# Rectifire_PFC_Solar.net
KiCad netlist of a schematic drawn in Altium Designer
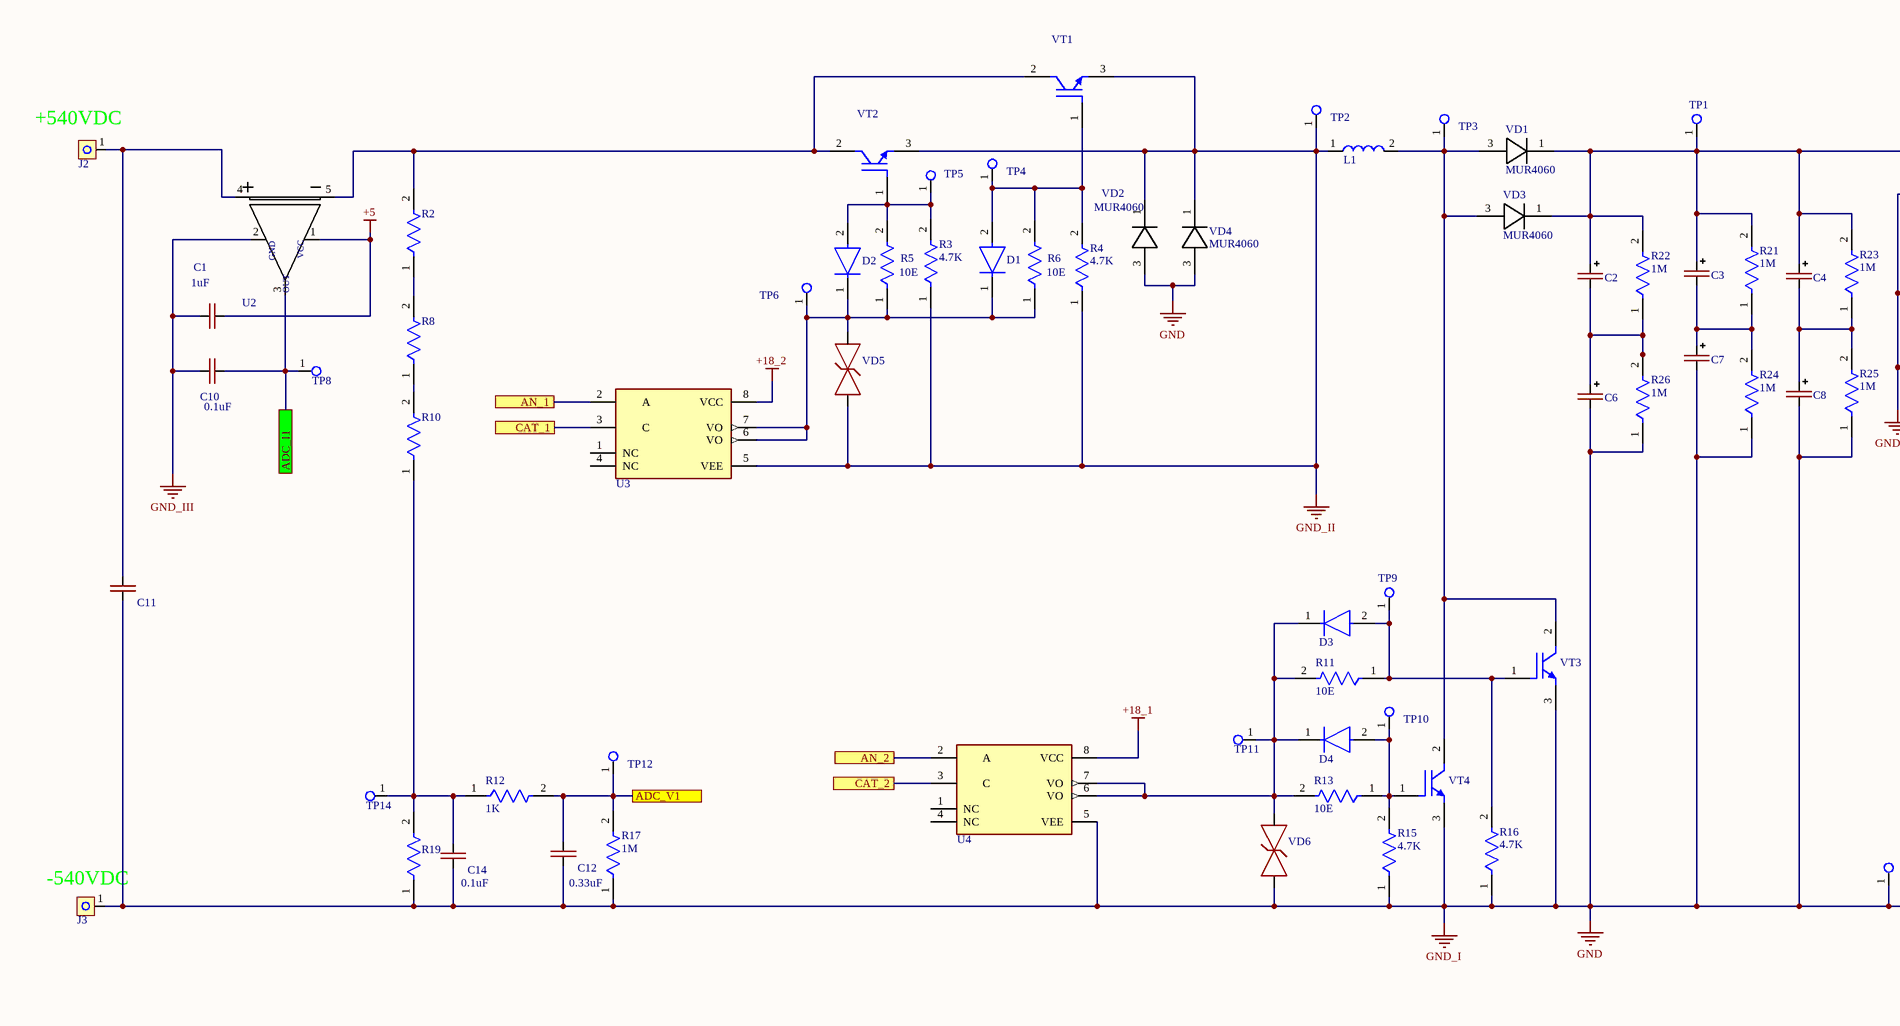
[diagram p0: Rectifire_PFC_Solar.SchDoc, top left]
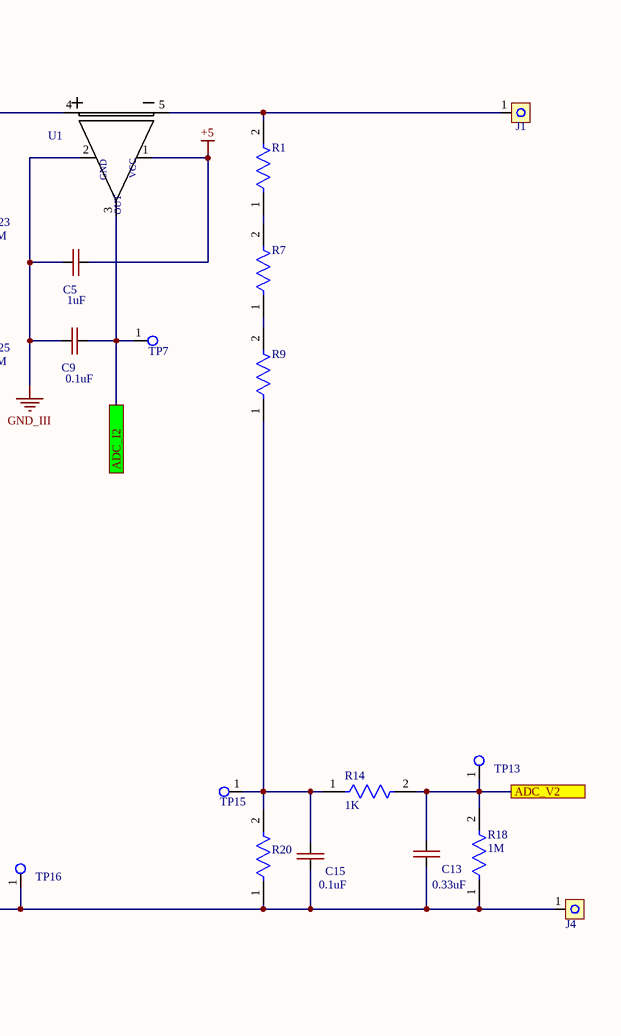
[diagram p1: Rectifire_PFC_Solar.SchDoc, top right]
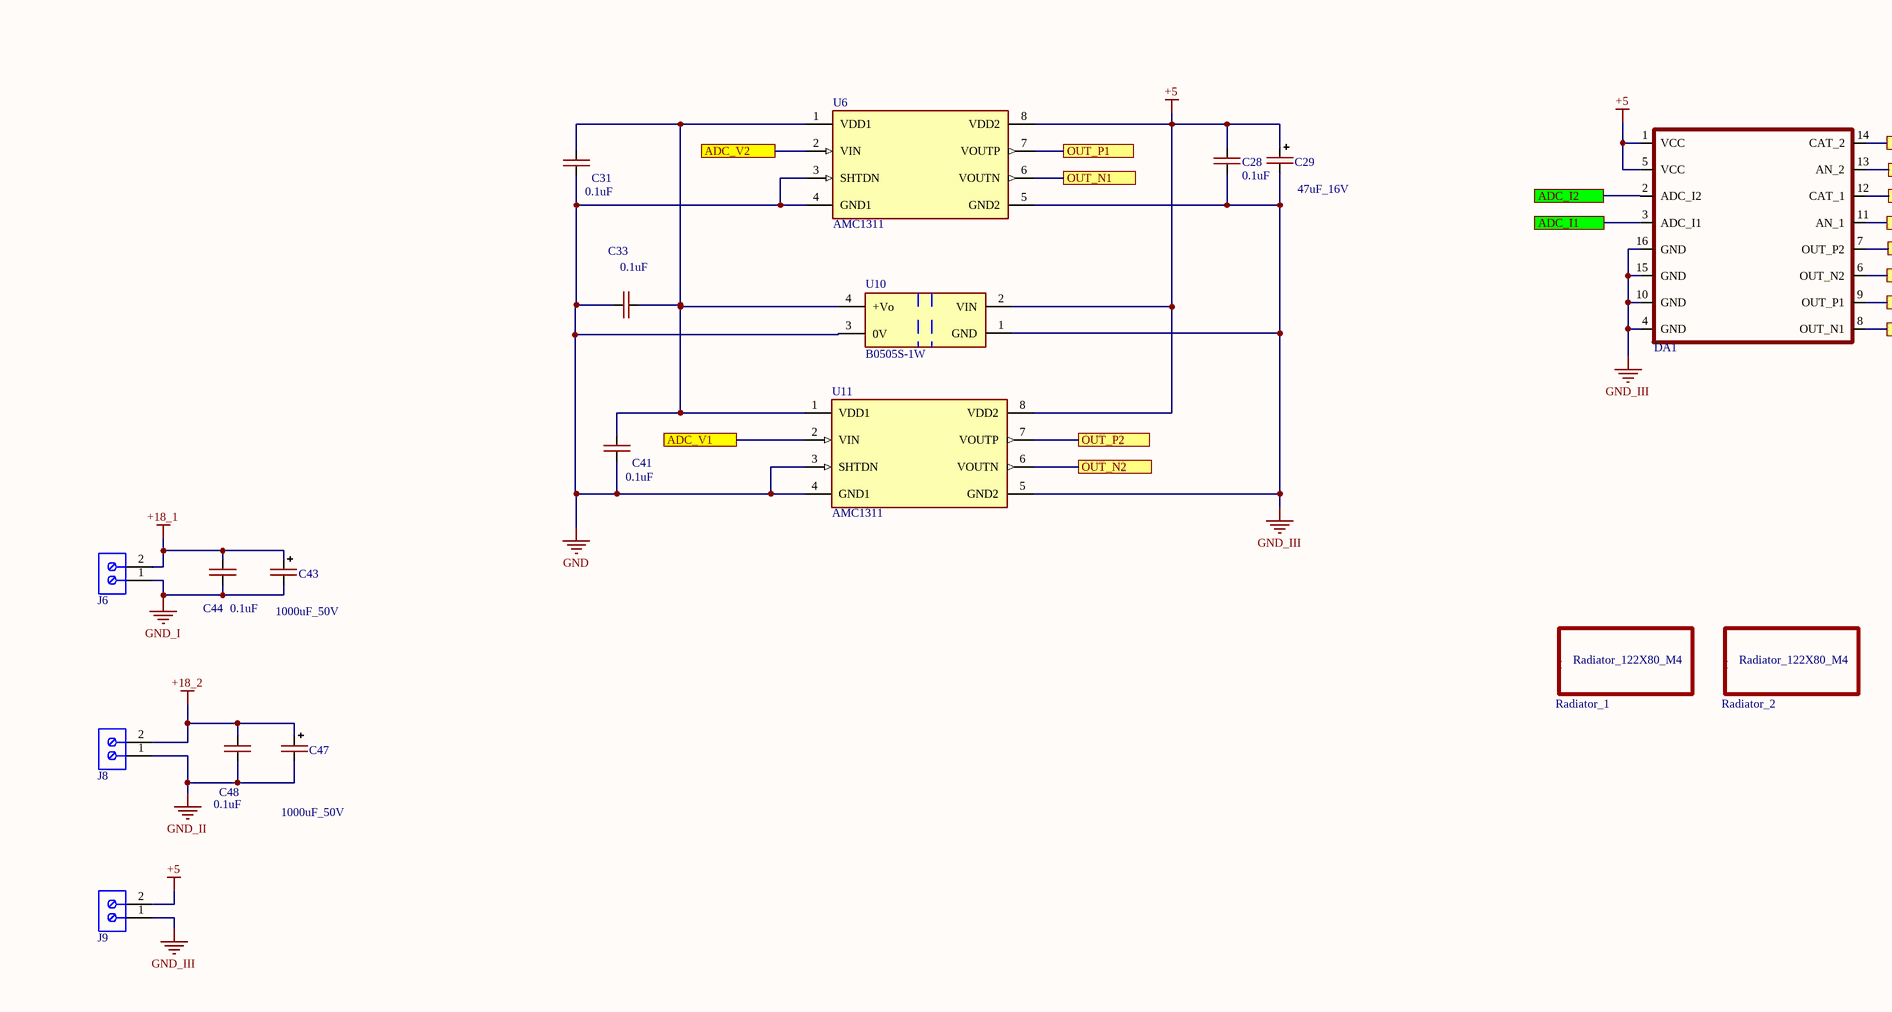
[diagram p2: Rectifire_PFC_Solar.SchDoc, bottom left]
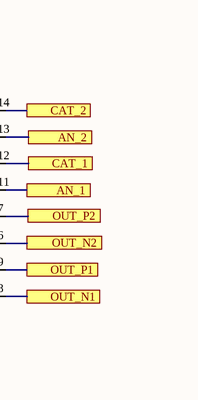
[diagram p3: Rectifire_PFC_Solar.SchDoc, bottom right]

(export (version "E")
  (design (tool "Eeschema 10.0.6"))
  (components
    (comp (ref "C1")
      (value "1uF")
      (footprint "CAP-0805")
      (libsource (lib "PASSIVE_COMPONENTS") (part "CAP-NON-POLAR"))
    )
    (comp (ref "C2")
      (value "CAP-POLAR")
      (footprint "CAP 100uF_500V 22x40mm")
      (libsource (lib "PASSIVE_COMPONENTS") (part "CAP-POLAR"))
    )
    (comp (ref "C3")
      (value "CAP-POLAR")
      (footprint "CAP 100uF_500V 22x40mm")
      (libsource (lib "PASSIVE_COMPONENTS") (part "CAP-POLAR"))
    )
    (comp (ref "C4")
      (value "CAP-POLAR")
      (footprint "CAP 100uF_500V 22x40mm")
      (libsource (lib "PASSIVE_COMPONENTS") (part "CAP-POLAR"))
    )
    (comp (ref "C5")
      (value "1uF")
      (footprint "CAP-0805")
      (libsource (lib "PASSIVE_COMPONENTS") (part "CAP-NON-POLAR"))
    )
    (comp (ref "C6")
      (value "CAP-POLAR")
      (footprint "CAP 100uF_500V 22x40mm")
      (libsource (lib "PASSIVE_COMPONENTS") (part "CAP-POLAR"))
    )
    (comp (ref "C7")
      (value "CAP-POLAR")
      (footprint "CAP 100uF_500V 22x40mm")
      (libsource (lib "PASSIVE_COMPONENTS") (part "CAP-POLAR"))
    )
    (comp (ref "C8")
      (value "CAP-POLAR")
      (footprint "CAP 100uF_500V 22x40mm")
      (libsource (lib "PASSIVE_COMPONENTS") (part "CAP-POLAR"))
    )
    (comp (ref "C9")
      (value "0.1uF")
      (footprint "CAP-0805")
      (libsource (lib "PASSIVE_COMPONENTS") (part "CAP-NON-POLAR"))
    )
    (comp (ref "C10")
      (value "0.1uF")
      (footprint "CAP-0805")
      (libsource (lib "PASSIVE_COMPONENTS") (part "CAP-NON-POLAR"))
    )
    (comp (ref "C11")
      (value "CAP-NON-POLAR")
      (footprint "CAP_4.7uF_630V")
      (libsource (lib "PASSIVE_COMPONENTS") (part "CAP-NON-POLAR"))
    )
    (comp (ref "C12")
      (value "0.33uF")
      (footprint "CAP-0805")
      (libsource (lib "PASSIVE_COMPONENTS") (part "CAP-NON-POLAR"))
    )
    (comp (ref "C13")
      (value "0.33uF")
      (footprint "CAP-0805")
      (libsource (lib "PASSIVE_COMPONENTS") (part "CAP-NON-POLAR"))
    )
    (comp (ref "C14")
      (value "0.1uF")
      (footprint "CAP-0805")
      (libsource (lib "PASSIVE_COMPONENTS") (part "CAP-NON-POLAR"))
    )
    (comp (ref "C15")
      (value "0.1uF")
      (footprint "CAP-0805")
      (libsource (lib "PASSIVE_COMPONENTS") (part "CAP-NON-POLAR"))
    )
    (comp (ref "C28")
      (value "0.1uF")
      (footprint "CAP-0805")
      (libsource (lib "PASSIVE_COMPONENTS") (part "CAP-NON-POLAR"))
    )
    (comp (ref "C29")
      (value "47uF_16V")
      (footprint "CAP-TAN-D")
      (libsource (lib "PASSIVE_COMPONENTS") (part "CAP-POLAR"))
    )
    (comp (ref "C31")
      (value "0.1uF")
      (footprint "CAP-0805")
      (libsource (lib "PASSIVE_COMPONENTS") (part "CAP-NON-POLAR"))
    )
    (comp (ref "C33")
      (value "0.1uF")
      (footprint "CAP-0805")
      (libsource (lib "PASSIVE_COMPONENTS") (part "CAP-NON-POLAR"))
    )
    (comp (ref "C41")
      (value "0.1uF")
      (footprint "CAP-0805")
      (libsource (lib "PASSIVE_COMPONENTS") (part "CAP-NON-POLAR"))
    )
    (comp (ref "C43")
      (value "1000uF_50V")
      (footprint "CAPPOL-16x25")
      (libsource (lib "PASSIVE_COMPONENTS") (part "CAP-POLAR"))
    )
    (comp (ref "C44")
      (value "0.1uF")
      (footprint "CAP-0805")
      (libsource (lib "PASSIVE_COMPONENTS") (part "CAP-NON-POLAR"))
    )
    (comp (ref "C47")
      (value "1000uF_50V")
      (footprint "CAPPOL-16x25")
      (libsource (lib "PASSIVE_COMPONENTS") (part "CAP-POLAR"))
    )
    (comp (ref "C48")
      (value "0.1uF")
      (footprint "CAP-0805")
      (libsource (lib "PASSIVE_COMPONENTS") (part "CAP-NON-POLAR"))
    )
    (comp (ref "D1") (value "US1G") (footprint "DO-214AA") (libsource (lib "Diodes") (part "US1G")))
    (comp (ref "D2") (value "US1G") (footprint "DO-214AA") (libsource (lib "Diodes") (part "US1G")))
    (comp (ref "D3") (value "US1G") (footprint "DO-214AA") (libsource (lib "Diodes") (part "US1G")))
    (comp (ref "D4") (value "US1G") (footprint "DO-214AA") (libsource (lib "Diodes") (part "US1G")))
    (comp (ref "DA1")
      (value "BOARD_PFC")
      (footprint "BOARD_PFC")
      (libsource (lib "BOARD_PFC") (part "BOARD_PFC"))
    )
    (comp (ref "J1")
      (value "MG_136_HT")
      (footprint "Conn_MEIGAN_MG136HT")
      (libsource (lib "") (part "Connector_MEIGAN_MG136HT_1"))
    )
    (comp (ref "J2")
      (value "MG_136_HT")
      (footprint "Conn_MEIGAN_MG136HT")
      (libsource (lib "Connectors") (part "Connector_MEIGAN_MG136HT"))
    )
    (comp (ref "J3")
      (value "MG_136_HT")
      (footprint "Conn_MEIGAN_MG136HT")
      (libsource (lib "Connectors") (part "Connector_MEIGAN_MG136HT"))
    )
    (comp (ref "J4")
      (value "MG_136_HT")
      (footprint "Conn_MEIGAN_MG136HT")
      (libsource (lib "") (part "Connector_MEIGAN_MG136HT_1"))
    )
    (comp (ref "J6")
      (value "691102710002")
      (footprint "691102710002")
      (description "WR-TBL Series 102 Horizontal Entry Modular, THT, pitch 5mm, 2p")
      (fields (field (name "MANUFACTURER") "Wurth Elektronik"))
      (libsource (lib "Altium_WR-TBL (rev23f)") (part "691102710002"))
    )
    (comp (ref "J8")
      (value "691102710002")
      (footprint "691102710002")
      (description "WR-TBL Series 102 Horizontal Entry Modular, THT, pitch 5mm, 2p")
      (fields (field (name "MANUFACTURER") "Wurth Elektronik"))
      (libsource (lib "Altium_WR-TBL (rev23f)") (part "691102710002"))
    )
    (comp (ref "J9")
      (value "691102710002")
      (footprint "691102710002")
      (description "WR-TBL Series 102 Horizontal Entry Modular, THT, pitch 5mm, 2p")
      (fields (field (name "MANUFACTURER") "Wurth Elektronik"))
      (libsource (lib "Altium_WR-TBL (rev23f)") (part "691102710002"))
    )
    (comp (ref "L1") (value "Coil") (footprint "30A_10uH") (libsource (lib "Transformers") (part "Coil")))
    (comp (ref "R1")
      (value "~")
      (footprint "RES-2512")
      (libsource (lib "PASSIVE_COMPONENTS") (part "RES-CONST"))
    )
    (comp (ref "R2")
      (value "~")
      (footprint "RES-2512")
      (libsource (lib "PASSIVE_COMPONENTS") (part "RES-CONST"))
    )
    (comp (ref "R3")
      (value "4.7K")
      (footprint "RES-0805")
      (libsource (lib "PASSIVE_COMPONENTS") (part "RES-CONST"))
    )
    (comp (ref "R4")
      (value "4.7K")
      (footprint "RES-0805")
      (libsource (lib "PASSIVE_COMPONENTS") (part "RES-CONST"))
    )
    (comp (ref "R5")
      (value "10E")
      (footprint "RES_SMD_1210_IPC_A")
      (libsource (lib "PASSIVE_COMPONENTS") (part "RES_1210"))
    )
    (comp (ref "R6")
      (value "10E")
      (footprint "RES_SMD_1210_IPC_A")
      (libsource (lib "PASSIVE_COMPONENTS") (part "RES_1210"))
    )
    (comp (ref "R7")
      (value "~")
      (footprint "RES-2512")
      (libsource (lib "PASSIVE_COMPONENTS") (part "RES-CONST"))
    )
    (comp (ref "R8")
      (value "~")
      (footprint "RES-2512")
      (libsource (lib "PASSIVE_COMPONENTS") (part "RES-CONST"))
    )
    (comp (ref "R9")
      (value "~")
      (footprint "RES-2512")
      (libsource (lib "PASSIVE_COMPONENTS") (part "RES-CONST"))
    )
    (comp (ref "R10")
      (value "~")
      (footprint "RES-2512")
      (libsource (lib "PASSIVE_COMPONENTS") (part "RES-CONST"))
    )
    (comp (ref "R11")
      (value "10E")
      (footprint "RES_SMD_1210_IPC_A")
      (libsource (lib "PASSIVE_COMPONENTS") (part "RES_1210"))
    )
    (comp (ref "R12")
      (value "1K")
      (footprint "RES-0805")
      (libsource (lib "PASSIVE_COMPONENTS") (part "RES-CONST"))
    )
    (comp (ref "R13")
      (value "10E")
      (footprint "RES_SMD_1210_IPC_A")
      (libsource (lib "PASSIVE_COMPONENTS") (part "RES_1210"))
    )
    (comp (ref "R14")
      (value "1K")
      (footprint "RES-0805")
      (libsource (lib "PASSIVE_COMPONENTS") (part "RES-CONST"))
    )
    (comp (ref "R15")
      (value "4.7K")
      (footprint "RES-0805")
      (libsource (lib "PASSIVE_COMPONENTS") (part "RES-CONST"))
    )
    (comp (ref "R16")
      (value "4.7K")
      (footprint "RES-0805")
      (libsource (lib "PASSIVE_COMPONENTS") (part "RES-CONST"))
    )
    (comp (ref "R17")
      (value "1M")
      (footprint "RES-0805")
      (libsource (lib "PASSIVE_COMPONENTS") (part "RES-CONST"))
    )
    (comp (ref "R18")
      (value "1M")
      (footprint "RES-0805")
      (libsource (lib "PASSIVE_COMPONENTS") (part "RES-CONST"))
    )
    (comp (ref "R19")
      (value "RES_1210")
      (footprint "RES_SMD_1210_IPC_B")
      (libsource (lib "PASSIVE_COMPONENTS") (part "RES_1210"))
    )
    (comp (ref "R20")
      (value "RES_1210")
      (footprint "RES_SMD_1210_IPC_B")
      (libsource (lib "PASSIVE_COMPONENTS") (part "RES_1210"))
    )
    (comp (ref "R21")
      (value "1M")
      (footprint "RES-2512")
      (description "4.7K")
      (libsource (lib "PASSIVE_COMPONENTS") (part "RES-CONST"))
    )
    (comp (ref "R22")
      (value "1M")
      (footprint "RES-2512")
      (description "4.7K")
      (libsource (lib "PASSIVE_COMPONENTS") (part "RES-CONST"))
    )
    (comp (ref "R23")
      (value "1M")
      (footprint "RES-2512")
      (description "4.7K")
      (libsource (lib "PASSIVE_COMPONENTS") (part "RES-CONST"))
    )
    (comp (ref "R24")
      (value "1M")
      (footprint "RES-2512")
      (description "4.7K")
      (libsource (lib "PASSIVE_COMPONENTS") (part "RES-CONST"))
    )
    (comp (ref "R25")
      (value "1M")
      (footprint "RES-2512")
      (description "4.7K")
      (libsource (lib "PASSIVE_COMPONENTS") (part "RES-CONST"))
    )
    (comp (ref "R26")
      (value "1M")
      (footprint "RES-2512")
      (description "4.7K")
      (libsource (lib "PASSIVE_COMPONENTS") (part "RES-CONST"))
    )
    (comp (ref "Radiator_1")
      (value "Radiator_122X80_M4")
      (footprint "Radiator_122X80_M4")
      (libsource (lib "Radiator_122X80_M4") (part "Radiator_122X80_M4"))
    )
    (comp (ref "Radiator_2")
      (value "Radiator_122X80_M4")
      (footprint "Radiator_122X80_M4")
      (libsource (lib "Radiator_122X80_M4") (part "Radiator_122X80_M4"))
    )
    (comp (ref "TP1")
      (value "Test_Point_PCB")
      (footprint "Test_Point")
      (description "Test_Point")
      (libsource (lib "Connectors") (part "TP_PCB?"))
    )
    (comp (ref "TP2")
      (value "Test_Point_PCB")
      (footprint "Test_Point")
      (description "Test_Point")
      (libsource (lib "Connectors") (part "TP_PCB?"))
    )
    (comp (ref "TP3")
      (value "Test_Point_PCB")
      (footprint "Test_Point")
      (description "Test_Point")
      (libsource (lib "Connectors") (part "TP_PCB?"))
    )
    (comp (ref "TP4")
      (value "Test_Point_PCB")
      (footprint "Test_Point")
      (description "Test_Point")
      (libsource (lib "Connectors") (part "TP_PCB?"))
    )
    (comp (ref "TP5")
      (value "Test_Point_PCB")
      (footprint "Test_Point")
      (description "Test_Point")
      (libsource (lib "Connectors") (part "TP_PCB?"))
    )
    (comp (ref "TP6")
      (value "Test_Point_PCB")
      (footprint "Test_Point")
      (description "Test_Point")
      (libsource (lib "Connectors") (part "TP_PCB?"))
    )
    (comp (ref "TP7")
      (value "Test_Point_PCB")
      (footprint "Test_Point")
      (description "Test_Point")
      (libsource (lib "Connectors") (part "TP_PCB?"))
    )
    (comp (ref "TP8")
      (value "Test_Point_PCB")
      (footprint "Test_Point")
      (description "Test_Point")
      (libsource (lib "Connectors") (part "TP_PCB?"))
    )
    (comp (ref "TP9")
      (value "Test_Point_PCB")
      (footprint "Test_Point")
      (description "Test_Point")
      (libsource (lib "Connectors") (part "TP_PCB?"))
    )
    (comp (ref "TP10")
      (value "Test_Point_PCB")
      (footprint "Test_Point")
      (description "Test_Point")
      (libsource (lib "Connectors") (part "TP_PCB?"))
    )
    (comp (ref "TP11")
      (value "Test_Point_PCB")
      (footprint "Test_Point")
      (description "Test_Point")
      (libsource (lib "Connectors") (part "TP_PCB?"))
    )
    (comp (ref "TP12")
      (value "Test_Point_PCB")
      (footprint "Test_Point")
      (description "Test_Point")
      (libsource (lib "Connectors") (part "TP_PCB?"))
    )
    (comp (ref "TP13")
      (value "Test_Point_PCB")
      (footprint "Test_Point")
      (description "Test_Point")
      (libsource (lib "Connectors") (part "TP_PCB?"))
    )
    (comp (ref "TP14")
      (value "Test_Point_PCB")
      (footprint "Test_Point")
      (description "Test_Point")
      (libsource (lib "Connectors") (part "TP_PCB?"))
    )
    (comp (ref "TP15")
      (value "Test_Point_PCB")
      (footprint "Test_Point")
      (description "Test_Point")
      (libsource (lib "Connectors") (part "TP_PCB?"))
    )
    (comp (ref "TP16")
      (value "Test_Point_PCB")
      (footprint "Test_Point")
      (description "Test_Point")
      (libsource (lib "Connectors") (part "TP_PCB?"))
    )
    (comp (ref "U1")
      (value "ACS758")
      (footprint "ACS758-100")
      (libsource (lib "Integrated_Circuts") (part "ACS758"))
    )
    (comp (ref "U2")
      (value "ACS758")
      (footprint "ACS758-100")
      (libsource (lib "Integrated_Circuts") (part "ACS758"))
    )
    (comp (ref "U3")
      (value "HCPL-3120")
      (footprint "HCPL-3120")
      (libsource (lib "Integrated_Circuts") (part "HCPL-3120"))
    )
    (comp (ref "U4")
      (value "HCPL-3120")
      (footprint "HCPL-3120")
      (libsource (lib "Integrated_Circuts") (part "HCPL-3120"))
    )
    (comp (ref "U6")
      (value "AMC1311")
      (footprint "FP-DWV0008A-MFG")
      (libsource (lib "Integrated_Circuts") (part "AMC1311"))
    )
    (comp (ref "U10")
      (value "B0505S-1W")
      (footprint "B0505S-1W")
      (libsource (lib "Integrated_Circuts") (part "B0505S-1W"))
    )
    (comp (ref "U11")
      (value "AMC1311")
      (footprint "FP-DWV0008A-MFG")
      (libsource (lib "Integrated_Circuts") (part "AMC1311"))
    )
    (comp (ref "VD1") (value "MUR4060") (footprint "TO-247-2") (libsource (lib "Diodes") (part "MUR4060")))
    (comp (ref "VD2") (value "MUR4060") (footprint "TO-247-2") (libsource (lib "Diodes") (part "MUR4060")))
    (comp (ref "VD3") (value "MUR4060") (footprint "TO-247-2") (libsource (lib "Diodes") (part "MUR4060")))
    (comp (ref "VD4") (value "MUR4060") (footprint "TO-247-2") (libsource (lib "Diodes") (part "MUR4060")))
    (comp (ref "VD5")
      (value "Suppressor")
      (footprint "DO-214AA")
      (libsource (lib "Diodes") (part "Suppressor"))
    )
    (comp (ref "VD6")
      (value "Suppressor")
      (footprint "DO-214AA")
      (libsource (lib "Diodes") (part "Suppressor"))
    )
    (comp (ref "VT1")
      (value "IGBT 60N120T")
      (footprint "TO-264-3")
      (description "IGBT 60N120T TO-264-3")
      (libsource (lib "Transistors") (part "IGBT 60N120T"))
    )
    (comp (ref "VT2")
      (value "IGBT 60N120T")
      (footprint "TO-264-3")
      (description "IGBT 60N120T TO-264-3")
      (libsource (lib "Transistors") (part "IGBT 60N120T"))
    )
    (comp (ref "VT3")
      (value "IGBT 60N120T")
      (footprint "TO-264-3")
      (description "IGBT 60N120T TO-264-3")
      (libsource (lib "Transistors") (part "IGBT 60N120T"))
    )
    (comp (ref "VT4")
      (value "IGBT 60N120T")
      (footprint "TO-264-3")
      (description "IGBT 60N120T TO-264-3")
      (libsource (lib "Transistors") (part "IGBT 60N120T"))
    )
  )
  (nets
    (net (code "1") (name "+5") (class "Default")
      (node (ref "C1") (pin "2") (pinfunction "2_2") (pintype "passive"))
      (node (ref "C28") (pin "1") (pinfunction "1_1") (pintype "passive"))
      (node (ref "C29") (pin "1") (pinfunction "+_1") (pintype "passive"))
      (node (ref "C5") (pin "2") (pinfunction "2_2") (pintype "passive"))
      (node (ref "DA1") (pin "1") (pinfunction "VCC_1") (pintype "passive"))
      (node (ref "DA1") (pin "5") (pinfunction "VCC_5") (pintype "passive"))
      (node (ref "J9") (pin "2") (pinfunction "2_2") (pintype "passive"))
      (node (ref "U1") (pin "1") (pinfunction "+VCC_1") (pintype "passive"))
      (node (ref "U10") (pin "2") (pinfunction "VIN_2") (pintype "power_in"))
      (node (ref "U11") (pin "8") (pinfunction "VDD2_8") (pintype "power_in"))
      (node (ref "U2") (pin "1") (pinfunction "+VCC_1") (pintype "passive"))
      (node (ref "U6") (pin "8") (pinfunction "VDD2_8") (pintype "power_in"))
    )
    (net (code "2") (name "+18_1") (class "Default")
      (node (ref "C43") (pin "1") (pinfunction "+_1") (pintype "passive"))
      (node (ref "C44") (pin "2") (pinfunction "2_2") (pintype "passive"))
      (node (ref "J6") (pin "2") (pinfunction "2_2") (pintype "passive"))
      (node (ref "U4") (pin "8") (pinfunction "VCC_8") (pintype "power_in"))
    )
    (net (code "3") (name "+18_2") (class "Default")
      (node (ref "C47") (pin "1") (pinfunction "+_1") (pintype "passive"))
      (node (ref "C48") (pin "2") (pinfunction "2_2") (pintype "passive"))
      (node (ref "J8") (pin "2") (pinfunction "2_2") (pintype "passive"))
      (node (ref "U3") (pin "8") (pinfunction "VCC_8") (pintype "power_in"))
    )
    (net (code "4") (name "/ADC_I1") (class "Default")
      (node (ref "C10") (pin "2") (pinfunction "2_2") (pintype "passive"))
      (node (ref "DA1") (pin "3") (pinfunction "ADC_I1_3") (pintype "passive"))
      (node (ref "TP8") (pin "1") (pinfunction "G9_1") (pintype "passive"))
      (node (ref "U2") (pin "3") (pinfunction "OUT_3") (pintype "passive"))
    )
    (net (code "5") (name "/ADC_I2") (class "Default")
      (node (ref "C9") (pin "2") (pinfunction "2_2") (pintype "passive"))
      (node (ref "DA1") (pin "2") (pinfunction "ADC_I2_2") (pintype "passive"))
      (node (ref "TP7") (pin "1") (pinfunction "G9_1") (pintype "passive"))
      (node (ref "U1") (pin "3") (pinfunction "OUT_3") (pintype "passive"))
    )
    (net (code "6") (name "/ADC_V1") (class "Default")
      (node (ref "C12") (pin "2") (pinfunction "2_2") (pintype "passive"))
      (node (ref "R12") (pin "2") (pinfunction "2_2") (pintype "passive"))
      (node (ref "R17") (pin "2") (pinfunction "2_2") (pintype "passive"))
      (node (ref "TP12") (pin "1") (pinfunction "G9_1") (pintype "passive"))
      (node (ref "U11") (pin "2") (pinfunction "VIN_2") (pintype "input"))
    )
    (net (code "7") (name "/ADC_V2") (class "Default")
      (node (ref "C13") (pin "2") (pinfunction "2_2") (pintype "passive"))
      (node (ref "R14") (pin "2") (pinfunction "2_2") (pintype "passive"))
      (node (ref "R18") (pin "2") (pinfunction "2_2") (pintype "passive"))
      (node (ref "TP13") (pin "1") (pinfunction "G9_1") (pintype "passive"))
      (node (ref "U6") (pin "2") (pinfunction "VIN_2") (pintype "input"))
    )
    (net (code "8") (name "/AN_1") (class "Default")
      (node (ref "DA1") (pin "11") (pinfunction "AN_1_11") (pintype "passive"))
      (node (ref "U3") (pin "2") (pinfunction "A_2") (pintype "passive"))
    )
    (net (code "9") (name "/AN_2") (class "Default")
      (node (ref "DA1") (pin "13") (pinfunction "AN_2_13") (pintype "passive"))
      (node (ref "U4") (pin "2") (pinfunction "A_2") (pintype "passive"))
    )
    (net (code "10") (name "/CAT_1") (class "Default")
      (node (ref "DA1") (pin "12") (pinfunction "CAT_1_12") (pintype "passive"))
      (node (ref "U3") (pin "3") (pinfunction "C_3") (pintype "passive"))
    )
    (net (code "11") (name "/CAT_2") (class "Default")
      (node (ref "DA1") (pin "14") (pinfunction "CAT_2_14") (pintype "passive"))
      (node (ref "U4") (pin "3") (pinfunction "C_3") (pintype "passive"))
    )
    (net (code "12") (name "/OUT_N1") (class "Default")
      (node (ref "DA1") (pin "8") (pinfunction "OUT_N1_8") (pintype "passive"))
      (node (ref "U6") (pin "6") (pinfunction "VOUTN_6") (pintype "output"))
    )
    (net (code "13") (name "/OUT_N2") (class "Default")
      (node (ref "DA1") (pin "6") (pinfunction "OUT_N2_6") (pintype "passive"))
      (node (ref "U11") (pin "6") (pinfunction "VOUTN_6") (pintype "output"))
    )
    (net (code "14") (name "/OUT_P1") (class "Default")
      (node (ref "DA1") (pin "9") (pinfunction "OUT_P1_9") (pintype "passive"))
      (node (ref "U6") (pin "7") (pinfunction "VOUTP_7") (pintype "output"))
    )
    (net (code "15") (name "/OUT_P2") (class "Default")
      (node (ref "DA1") (pin "7") (pinfunction "OUT_P2_7") (pintype "passive"))
      (node (ref "U11") (pin "7") (pinfunction "VOUTP_7") (pintype "output"))
    )
    (net (code "16") (name "GND") (class "Default")
      (node (ref "C11") (pin "1") (pinfunction "1_1") (pintype "passive"))
      (node (ref "C12") (pin "1") (pinfunction "1_1") (pintype "passive"))
      (node (ref "C13") (pin "1") (pinfunction "1_1") (pintype "passive"))
      (node (ref "C14") (pin "1") (pinfunction "1_1") (pintype "passive"))
      (node (ref "C15") (pin "1") (pinfunction "1_1") (pintype "passive"))
      (node (ref "C31") (pin "1") (pinfunction "1_1") (pintype "passive"))
      (node (ref "C33") (pin "2") (pinfunction "2_2") (pintype "passive"))
      (node (ref "C41") (pin "1") (pinfunction "1_1") (pintype "passive"))
      (node (ref "C43") (pin "2") (pinfunction "-_2") (pintype "passive"))
      (node (ref "C44") (pin "1") (pinfunction "1_1") (pintype "passive"))
      (node (ref "C6") (pin "2") (pinfunction "-_2") (pintype "passive"))
      (node (ref "C7") (pin "2") (pinfunction "-_2") (pintype "passive"))
      (node (ref "C8") (pin "2") (pinfunction "-_2") (pintype "passive"))
      (node (ref "J3") (pin "1") (pinfunction "17_1") (pintype "passive"))
      (node (ref "J4") (pin "1") (pinfunction "17_1") (pintype "passive"))
      (node (ref "J6") (pin "1") (pinfunction "1_1") (pintype "passive"))
      (node (ref "R15") (pin "1") (pinfunction "1_1") (pintype "passive"))
      (node (ref "R16") (pin "1") (pinfunction "1_1") (pintype "passive"))
      (node (ref "R17") (pin "1") (pinfunction "1_1") (pintype "passive"))
      (node (ref "R18") (pin "1") (pinfunction "1_1") (pintype "passive"))
      (node (ref "R19") (pin "1") (pinfunction "1_1") (pintype "passive"))
      (node (ref "R20") (pin "1") (pinfunction "1_1") (pintype "passive"))
      (node (ref "R24") (pin "1") (pinfunction "1_1") (pintype "passive"))
      (node (ref "R25") (pin "1") (pinfunction "1_1") (pintype "passive"))
      (node (ref "R26") (pin "1") (pinfunction "1_1") (pintype "passive"))
      (node (ref "TP16") (pin "1") (pinfunction "G9_1") (pintype "passive"))
      (node (ref "U10") (pin "3") (pinfunction "0V_3") (pintype "power_in"))
      (node (ref "U11") (pin "3") (pinfunction "SHTDN_3") (pintype "input"))
      (node (ref "U11") (pin "4") (pinfunction "GND1_4") (pintype "power_in"))
      (node (ref "U4") (pin "5") (pinfunction "VEE_5") (pintype "power_in"))
      (node (ref "U6") (pin "3") (pinfunction "SHTDN_3") (pintype "input"))
      (node (ref "U6") (pin "4") (pinfunction "GND1_4") (pintype "power_in"))
      (node (ref "VD2") (pin "3") (pinfunction "3_3") (pintype "passive"))
      (node (ref "VD4") (pin "3") (pinfunction "3_3") (pintype "passive"))
      (node (ref "VD6") (pin "1") (pinfunction "C_1") (pintype "passive"))
      (node (ref "VT3") (pin "3") (pinfunction "E_3") (pintype "passive"))
      (node (ref "VT4") (pin "3") (pinfunction "E_3") (pintype "passive"))
    )
    (net (code "17") (name "GND_II") (class "Default")
      (node (ref "C47") (pin "2") (pinfunction "-_2") (pintype "passive"))
      (node (ref "C48") (pin "1") (pinfunction "1_1") (pintype "passive"))
      (node (ref "J8") (pin "1") (pinfunction "1_1") (pintype "passive"))
      (node (ref "L1") (pin "1") (pinfunction "1_1") (pintype "passive"))
      (node (ref "R3") (pin "1") (pinfunction "1_1") (pintype "passive"))
      (node (ref "R4") (pin "1") (pinfunction "1_1") (pintype "passive"))
      (node (ref "TP2") (pin "1") (pinfunction "G9_1") (pintype "passive"))
      (node (ref "U3") (pin "5") (pinfunction "VEE_5") (pintype "power_in"))
      (node (ref "VD2") (pin "1") (pinfunction "1_1") (pintype "passive"))
      (node (ref "VD4") (pin "1") (pinfunction "1_1") (pintype "passive"))
      (node (ref "VD5") (pin "1") (pinfunction "C_1") (pintype "passive"))
      (node (ref "VT1") (pin "3") (pinfunction "E_3") (pintype "passive"))
      (node (ref "VT2") (pin "3") (pinfunction "E_3") (pintype "passive"))
    )
    (net (code "18") (name "GND_III") (class "Default")
      (node (ref "C1") (pin "1") (pinfunction "1_1") (pintype "passive"))
      (node (ref "C10") (pin "1") (pinfunction "1_1") (pintype "passive"))
      (node (ref "C28") (pin "2") (pinfunction "2_2") (pintype "passive"))
      (node (ref "C29") (pin "2") (pinfunction "-_2") (pintype "passive"))
      (node (ref "C5") (pin "1") (pinfunction "1_1") (pintype "passive"))
      (node (ref "C9") (pin "1") (pinfunction "1_1") (pintype "passive"))
      (node (ref "DA1") (pin "10") (pinfunction "GND_10") (pintype "passive"))
      (node (ref "DA1") (pin "15") (pinfunction "GND_15") (pintype "passive"))
      (node (ref "DA1") (pin "16") (pinfunction "GND_16") (pintype "passive"))
      (node (ref "DA1") (pin "4") (pinfunction "GND_4") (pintype "passive"))
      (node (ref "J9") (pin "1") (pinfunction "1_1") (pintype "passive"))
      (node (ref "U1") (pin "2") (pinfunction "GND_2") (pintype "passive"))
      (node (ref "U10") (pin "1") (pinfunction "GND_1") (pintype "power_in"))
      (node (ref "U11") (pin "5") (pinfunction "GND2_5") (pintype "power_in"))
      (node (ref "U2") (pin "2") (pinfunction "GND_2") (pintype "passive"))
      (node (ref "U6") (pin "5") (pinfunction "GND2_5") (pintype "power_in"))
    )
    (net (code "19") (name "Net-(C2-+)") (class "Default")
      (node (ref "C2") (pin "1") (pinfunction "+_1") (pintype "passive"))
      (node (ref "C3") (pin "1") (pinfunction "+_1") (pintype "passive"))
      (node (ref "C4") (pin "1") (pinfunction "+_1") (pintype "passive"))
      (node (ref "R21") (pin "2") (pinfunction "2_2") (pintype "passive"))
      (node (ref "R22") (pin "2") (pinfunction "2_2") (pintype "passive"))
      (node (ref "R23") (pin "2") (pinfunction "2_2") (pintype "passive"))
      (node (ref "TP1") (pin "1") (pinfunction "G9_1") (pintype "passive"))
      (node (ref "U1") (pin "4") (pinfunction "+IP_4") (pintype "passive"))
      (node (ref "VD1") (pin "1") (pinfunction "1_1") (pintype "passive"))
      (node (ref "VD3") (pin "1") (pinfunction "1_1") (pintype "passive"))
    )
    (net (code "20") (name "Net-(C2--)") (class "Default")
      (node (ref "C2") (pin "2") (pinfunction "-_2") (pintype "passive"))
      (node (ref "C6") (pin "1") (pinfunction "+_1") (pintype "passive"))
      (node (ref "R22") (pin "1") (pinfunction "1_1") (pintype "passive"))
      (node (ref "R26") (pin "2") (pinfunction "2_2") (pintype "passive"))
    )
    (net (code "21") (name "Net-(C3--)") (class "Default")
      (node (ref "C3") (pin "2") (pinfunction "-_2") (pintype "passive"))
      (node (ref "C7") (pin "1") (pinfunction "+_1") (pintype "passive"))
      (node (ref "R21") (pin "1") (pinfunction "1_1") (pintype "passive"))
      (node (ref "R24") (pin "2") (pinfunction "2_2") (pintype "passive"))
    )
    (net (code "22") (name "Net-(C4--)") (class "Default")
      (node (ref "C4") (pin "2") (pinfunction "-_2") (pintype "passive"))
      (node (ref "C8") (pin "1") (pinfunction "+_1") (pintype "passive"))
      (node (ref "R23") (pin "1") (pinfunction "1_1") (pintype "passive"))
      (node (ref "R25") (pin "2") (pinfunction "2_2") (pintype "passive"))
    )
    (net (code "23") (name "Net-(D1-A)") (class "Default")
      (node (ref "D1") (pin "2") (pinfunction "A_2") (pintype "passive"))
      (node (ref "R4") (pin "2") (pinfunction "2_2") (pintype "passive"))
      (node (ref "R6") (pin "2") (pinfunction "2_2") (pintype "passive"))
      (node (ref "TP4") (pin "1") (pinfunction "G9_1") (pintype "passive"))
      (node (ref "VT1") (pin "1") (pinfunction "G_1") (pintype "passive"))
    )
    (net (code "24") (name "Net-(D1-C)") (class "Default")
      (node (ref "D1") (pin "1") (pinfunction "C_1") (pintype "passive"))
      (node (ref "D2") (pin "1") (pinfunction "C_1") (pintype "passive"))
      (node (ref "R5") (pin "1") (pinfunction "1_1") (pintype "passive"))
      (node (ref "R6") (pin "1") (pinfunction "1_1") (pintype "passive"))
      (node (ref "TP6") (pin "1") (pinfunction "G9_1") (pintype "passive"))
      (node (ref "U3") (pin "6") (pinfunction "VO_6") (pintype "output"))
      (node (ref "U3") (pin "7") (pinfunction "VO_7") (pintype "output"))
      (node (ref "VD5") (pin "2") (pinfunction "A_2") (pintype "passive"))
    )
    (net (code "25") (name "Net-(D2-A)") (class "Default")
      (node (ref "D2") (pin "2") (pinfunction "A_2") (pintype "passive"))
      (node (ref "R3") (pin "2") (pinfunction "2_2") (pintype "passive"))
      (node (ref "R5") (pin "2") (pinfunction "2_2") (pintype "passive"))
      (node (ref "TP5") (pin "1") (pinfunction "G9_1") (pintype "passive"))
      (node (ref "VT2") (pin "1") (pinfunction "G_1") (pintype "passive"))
    )
    (net (code "26") (name "Net-(D3-A)") (class "Default")
      (node (ref "D3") (pin "2") (pinfunction "A_2") (pintype "passive"))
      (node (ref "R11") (pin "1") (pinfunction "1_1") (pintype "passive"))
      (node (ref "R16") (pin "2") (pinfunction "2_2") (pintype "passive"))
      (node (ref "TP9") (pin "1") (pinfunction "G9_1") (pintype "passive"))
      (node (ref "VT3") (pin "1") (pinfunction "G_1") (pintype "passive"))
    )
    (net (code "27") (name "Net-(D3-C)") (class "Default")
      (node (ref "D3") (pin "1") (pinfunction "C_1") (pintype "passive"))
      (node (ref "D4") (pin "1") (pinfunction "C_1") (pintype "passive"))
      (node (ref "R11") (pin "2") (pinfunction "2_2") (pintype "passive"))
      (node (ref "R13") (pin "2") (pinfunction "2_2") (pintype "passive"))
      (node (ref "TP11") (pin "1") (pinfunction "G9_1") (pintype "passive"))
      (node (ref "U4") (pin "6") (pinfunction "VO_6") (pintype "output"))
      (node (ref "U4") (pin "7") (pinfunction "VO_7") (pintype "output"))
      (node (ref "VD6") (pin "2") (pinfunction "A_2") (pintype "passive"))
    )
    (net (code "28") (name "Net-(D4-A)") (class "Default")
      (node (ref "D4") (pin "2") (pinfunction "A_2") (pintype "passive"))
      (node (ref "R13") (pin "1") (pinfunction "1_1") (pintype "passive"))
      (node (ref "R15") (pin "2") (pinfunction "2_2") (pintype "passive"))
      (node (ref "TP10") (pin "1") (pinfunction "G9_1") (pintype "passive"))
      (node (ref "VT4") (pin "1") (pinfunction "G_1") (pintype "passive"))
    )
    (net (code "29") (name "Net-(J1-17)") (class "Default")
      (node (ref "J1") (pin "1") (pinfunction "17_1") (pintype "passive"))
      (node (ref "R1") (pin "2") (pinfunction "2_2") (pintype "passive"))
      (node (ref "U1") (pin "5") (pinfunction "-IP_5") (pintype "passive"))
    )
    (net (code "30") (name "Net-(J2-17)") (class "Default")
      (node (ref "C11") (pin "2") (pinfunction "2_2") (pintype "passive"))
      (node (ref "J2") (pin "1") (pinfunction "17_1") (pintype "passive"))
      (node (ref "U2") (pin "4") (pinfunction "+IP_4") (pintype "passive"))
    )
    (net (code "31") (name "Net-(R1-Pad1)") (class "Default")
      (node (ref "R1") (pin "1") (pinfunction "1_1") (pintype "passive"))
      (node (ref "R7") (pin "2") (pinfunction "2_2") (pintype "passive"))
    )
    (net (code "32") (name "Net-(R2-Pad1)") (class "Default")
      (node (ref "R2") (pin "1") (pinfunction "1_1") (pintype "passive"))
      (node (ref "R8") (pin "2") (pinfunction "2_2") (pintype "passive"))
    )
    (net (code "33") (name "Net-(R7-Pad1)") (class "Default")
      (node (ref "R7") (pin "1") (pinfunction "1_1") (pintype "passive"))
      (node (ref "R9") (pin "2") (pinfunction "2_2") (pintype "passive"))
    )
    (net (code "34") (name "Net-(R10-Pad2)") (class "Default")
      (node (ref "R10") (pin "2") (pinfunction "2_2") (pintype "passive"))
      (node (ref "R8") (pin "1") (pinfunction "1_1") (pintype "passive"))
    )
    (net (code "35") (name "Net-(TP3-G9)") (class "Default")
      (node (ref "L1") (pin "2") (pinfunction "2_2") (pintype "passive"))
      (node (ref "TP3") (pin "1") (pinfunction "G9_1") (pintype "passive"))
      (node (ref "VD1") (pin "3") (pinfunction "3_3") (pintype "passive"))
      (node (ref "VD3") (pin "3") (pinfunction "3_3") (pintype "passive"))
      (node (ref "VT3") (pin "2") (pinfunction "C_2") (pintype "passive"))
      (node (ref "VT4") (pin "2") (pinfunction "C_2") (pintype "passive"))
    )
    (net (code "36") (name "Net-(TP14-G9)") (class "Default")
      (node (ref "C14") (pin "2") (pinfunction "2_2") (pintype "passive"))
      (node (ref "R10") (pin "1") (pinfunction "1_1") (pintype "passive"))
      (node (ref "R12") (pin "1") (pinfunction "1_1") (pintype "passive"))
      (node (ref "R19") (pin "2") (pinfunction "2_2") (pintype "passive"))
      (node (ref "TP14") (pin "1") (pinfunction "G9_1") (pintype "passive"))
    )
    (net (code "37") (name "Net-(TP15-G9)") (class "Default")
      (node (ref "C15") (pin "2") (pinfunction "2_2") (pintype "passive"))
      (node (ref "R14") (pin "1") (pinfunction "1_1") (pintype "passive"))
      (node (ref "R20") (pin "2") (pinfunction "2_2") (pintype "passive"))
      (node (ref "R9") (pin "1") (pinfunction "1_1") (pintype "passive"))
      (node (ref "TP15") (pin "1") (pinfunction "G9_1") (pintype "passive"))
    )
    (net (code "38") (name "Net-(U2--IP)") (class "Default")
      (node (ref "R2") (pin "2") (pinfunction "2_2") (pintype "passive"))
      (node (ref "U2") (pin "5") (pinfunction "-IP_5") (pintype "passive"))
      (node (ref "VT1") (pin "2") (pinfunction "C_2") (pintype "passive"))
      (node (ref "VT2") (pin "2") (pinfunction "C_2") (pintype "passive"))
    )
    (net (code "39") (name "Net-(U10-+Vo)") (class "Default")
      (node (ref "C31") (pin "2") (pinfunction "2_2") (pintype "passive"))
      (node (ref "C33") (pin "1") (pinfunction "1_1") (pintype "passive"))
      (node (ref "C41") (pin "2") (pinfunction "2_2") (pintype "passive"))
      (node (ref "U10") (pin "4") (pinfunction "+Vo_4") (pintype "power_in"))
      (node (ref "U11") (pin "1") (pinfunction "VDD1_1") (pintype "power_in"))
      (node (ref "U6") (pin "1") (pinfunction "VDD1_1") (pintype "power_in"))
    )
    (net (code "40") (name "unconnected-(U3-NC-Pad1)") (class "Default")
      (node (ref "U3") (pin "1") (pinfunction "NC_1") (pintype "passive"))
    )
    (net (code "41") (name "unconnected-(U3-NC-Pad4)") (class "Default")
      (node (ref "U3") (pin "4") (pinfunction "NC_4") (pintype "passive"))
    )
    (net (code "42") (name "unconnected-(U4-NC-Pad1)") (class "Default")
      (node (ref "U4") (pin "1") (pinfunction "NC_1") (pintype "passive"))
    )
    (net (code "43") (name "unconnected-(U4-NC-Pad4)") (class "Default")
      (node (ref "U4") (pin "4") (pinfunction "NC_4") (pintype "passive"))
    )
  )
)
